# circuitPendulumController01.net
KiCad netlist of a schematic drawn in EAGLE
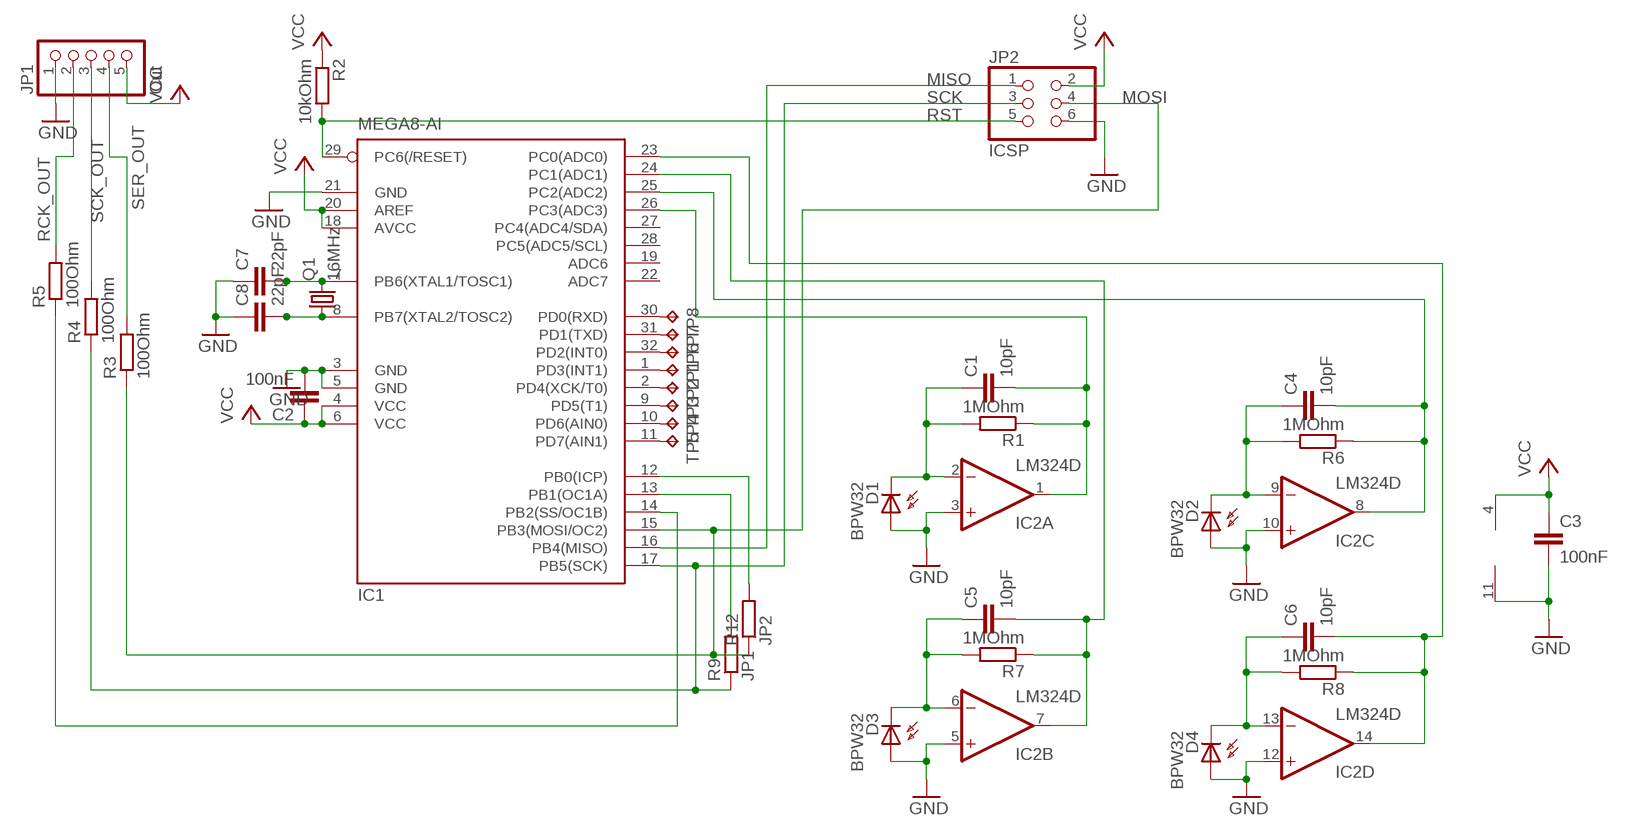
[diagram p0: schematic, sheet 1]

(export (version "E")
  (design (tool "Eeschema 10.0.6"))
  (components
    (comp (ref "C1")
      (value "10pF")
      (footprint "eagle-import:C0603")
      (libsource (lib "eagle-import") (part "C-EUC0603"))
    )
    (comp (ref "C2")
      (value "100nF")
      (footprint "eagle-import:C0603")
      (libsource (lib "eagle-import") (part "C-EUC0603"))
    )
    (comp (ref "C3")
      (value "100nF")
      (footprint "eagle-import:C0603")
      (libsource (lib "eagle-import") (part "C-EUC0603"))
    )
    (comp (ref "C4")
      (value "10pF")
      (footprint "eagle-import:C0603")
      (libsource (lib "eagle-import") (part "C-EUC0603"))
    )
    (comp (ref "C5")
      (value "10pF")
      (footprint "eagle-import:C0603")
      (libsource (lib "eagle-import") (part "C-EUC0603"))
    )
    (comp (ref "C6")
      (value "10pF")
      (footprint "eagle-import:C0603")
      (libsource (lib "eagle-import") (part "C-EUC0603"))
    )
    (comp (ref "C7")
      (value "22pF")
      (footprint "eagle-import:C0603")
      (libsource (lib "eagle-import") (part "C-EUC0603"))
    )
    (comp (ref "C8")
      (value "22pF")
      (footprint "eagle-import:C0603")
      (libsource (lib "eagle-import") (part "C-EUC0603"))
    )
    (comp (ref "D1")
      (value "BPW32")
      (footprint "eagle-import:BPW32")
      (libsource (lib "eagle-import") (part "BPW32"))
    )
    (comp (ref "D2")
      (value "BPW32")
      (footprint "eagle-import:BPW32")
      (libsource (lib "eagle-import") (part "BPW32"))
    )
    (comp (ref "D3")
      (value "BPW32")
      (footprint "eagle-import:BPW32")
      (libsource (lib "eagle-import") (part "BPW32"))
    )
    (comp (ref "D4")
      (value "BPW32")
      (footprint "eagle-import:BPW32")
      (libsource (lib "eagle-import") (part "BPW32"))
    )
    (comp (ref "IC1")
      (value "MEGA8-AI")
      (footprint "eagle-import:TQFP32-08")
      (fields (field (name "MPN") "ATMEGA8-16AU"))
      (libsource (lib "eagle-import") (part "MEGA8-AI"))
    )
    (comp (ref "IC2")
      (value "LM324D")
      (footprint "eagle-import:SO14")
      (libsource (lib "eagle-import") (part "LM324D"))
    )
    (comp (ref "JP1")
      (value "Out")
      (footprint "eagle-import:1_05X2MM")
      (libsource (lib "eagle-import") (part "PINHD-1X55X2MM"))
    )
    (comp (ref "JP2")
      (value "ICSP")
      (footprint "eagle-import:2X03")
      (libsource (lib "eagle-import") (part "PINHD-2X3"))
    )
    (comp (ref "Q1")
      (value "16MHz")
      (footprint "eagle-import:HC49_S")
      (libsource (lib "eagle-import") (part "CRYSTALHC49S"))
    )
    (comp (ref "R1")
      (value "1MOhm")
      (footprint "eagle-import:R0603")
      (libsource (lib "eagle-import") (part "R-EU_R0603"))
    )
    (comp (ref "R2")
      (value "10kOhm")
      (footprint "eagle-import:R0603")
      (libsource (lib "eagle-import") (part "R-EU_R0603"))
    )
    (comp (ref "R3")
      (value "100Ohm")
      (footprint "eagle-import:R0603")
      (libsource (lib "eagle-import") (part "R-EU_R0603"))
    )
    (comp (ref "R4")
      (value "100Ohm")
      (footprint "eagle-import:R0603")
      (libsource (lib "eagle-import") (part "R-EU_R0603"))
    )
    (comp (ref "R5")
      (value "100Ohm")
      (footprint "eagle-import:R0603")
      (libsource (lib "eagle-import") (part "R-EU_R0603"))
    )
    (comp (ref "R6")
      (value "1MOhm")
      (footprint "eagle-import:R0603")
      (libsource (lib "eagle-import") (part "R-EU_R0603"))
    )
    (comp (ref "R7")
      (value "1MOhm")
      (footprint "eagle-import:R0603")
      (libsource (lib "eagle-import") (part "R-EU_R0603"))
    )
    (comp (ref "R8")
      (value "1MOhm")
      (footprint "eagle-import:R0603")
      (libsource (lib "eagle-import") (part "R-EU_R0603"))
    )
    (comp (ref "R9")
      (value "JP1")
      (footprint "eagle-import:R0402")
      (libsource (lib "eagle-import") (part "R-EU_R0402"))
    )
    (comp (ref "R12")
      (value "JP2")
      (footprint "eagle-import:R0402")
      (libsource (lib "eagle-import") (part "R-EU_R0402"))
    )
    (comp (ref "TP1")
      (value "TPTP11R")
      (footprint "eagle-import:TP11R")
      (libsource (lib "eagle-import") (part "TPTP11R"))
    )
    (comp (ref "TP2")
      (value "TPTP11R")
      (footprint "eagle-import:TP11R")
      (libsource (lib "eagle-import") (part "TPTP11R"))
    )
    (comp (ref "TP3")
      (value "TPTP11R")
      (footprint "eagle-import:TP11R")
      (libsource (lib "eagle-import") (part "TPTP11R"))
    )
    (comp (ref "TP4")
      (value "TPTP11R")
      (footprint "eagle-import:TP11R")
      (libsource (lib "eagle-import") (part "TPTP11R"))
    )
    (comp (ref "TP5")
      (value "TPTP11R")
      (footprint "eagle-import:TP11R")
      (libsource (lib "eagle-import") (part "TPTP11R"))
    )
    (comp (ref "TP6")
      (value "TPTP11R")
      (footprint "eagle-import:TP11R")
      (libsource (lib "eagle-import") (part "TPTP11R"))
    )
    (comp (ref "TP7")
      (value "TPTP11R")
      (footprint "eagle-import:TP11R")
      (libsource (lib "eagle-import") (part "TPTP11R"))
    )
    (comp (ref "TP8")
      (value "TPTP11R")
      (footprint "eagle-import:TP11R")
      (libsource (lib "eagle-import") (part "TPTP11R"))
    )
  )
  (nets
    (net (code "1") (name "/MISO") (class "Default")
      (node (ref "IC1") (pin "16") (pinfunction "PB4(MISO)_16") (pintype "bidirectional"))
      (node (ref "JP2") (pin "1") (pinfunction "1_1") (pintype "passive"))
    )
    (net (code "2") (name "/MOSI") (class "Default")
      (node (ref "IC1") (pin "15") (pinfunction "PB3(MOSI/OC2)_15") (pintype "bidirectional"))
      (node (ref "JP2") (pin "4") (pinfunction "4_4") (pintype "passive"))
      (node (ref "R12") (pin "1") (pinfunction "1_1") (pintype "passive"))
      (node (ref "R3") (pin "1") (pinfunction "1_1") (pintype "passive"))
    )
    (net (code "3") (name "/RCK_OUT") (class "Default")
      (node (ref "JP1") (pin "2") (pinfunction "2_2") (pintype "passive"))
      (node (ref "R5") (pin "2") (pinfunction "2_2") (pintype "passive"))
    )
    (net (code "4") (name "/RST") (class "Default")
      (node (ref "IC1") (pin "29") (pinfunction "PC6(/RESET)_29") (pintype "bidirectional"))
      (node (ref "JP2") (pin "5") (pinfunction "5_5") (pintype "passive"))
      (node (ref "R2") (pin "2") (pinfunction "2_2") (pintype "passive"))
    )
    (net (code "5") (name "/SCK") (class "Default")
      (node (ref "IC1") (pin "17") (pinfunction "PB5(SCK)_17") (pintype "bidirectional"))
      (node (ref "JP2") (pin "3") (pinfunction "3_3") (pintype "passive"))
      (node (ref "R4") (pin "1") (pinfunction "1_1") (pintype "passive"))
      (node (ref "R9") (pin "1") (pinfunction "1_1") (pintype "passive"))
    )
    (net (code "6") (name "/SCK_OUT") (class "Default")
      (node (ref "JP1") (pin "3") (pinfunction "3_3") (pintype "passive"))
      (node (ref "R4") (pin "2") (pinfunction "2_2") (pintype "passive"))
    )
    (net (code "7") (name "/SER_OUT") (class "Default")
      (node (ref "JP1") (pin "4") (pinfunction "4_4") (pintype "passive"))
      (node (ref "R3") (pin "2") (pinfunction "2_2") (pintype "passive"))
    )
    (net (code "8") (name "GND") (class "Default")
      (node (ref "C2") (pin "2") (pinfunction "2_2") (pintype "passive"))
      (node (ref "C3") (pin "2") (pinfunction "2_2") (pintype "passive"))
      (node (ref "C7") (pin "1") (pinfunction "1_1") (pintype "passive"))
      (node (ref "C8") (pin "1") (pinfunction "1_1") (pintype "passive"))
      (node (ref "D1") (pin "A") (pinfunction "A_A") (pintype "passive"))
      (node (ref "D2") (pin "A") (pinfunction "A_A") (pintype "passive"))
      (node (ref "D3") (pin "A") (pinfunction "A_A") (pintype "passive"))
      (node (ref "D4") (pin "A") (pinfunction "A_A") (pintype "passive"))
      (node (ref "IC1") (pin "21") (pinfunction "GND_21") (pintype "power_in"))
      (node (ref "IC1") (pin "3") (pinfunction "GND_3") (pintype "power_in"))
      (node (ref "IC1") (pin "5") (pinfunction "GND_5") (pintype "power_in"))
      (node (ref "IC2") (pin "10") (pinfunction "+IN_10") (pintype "input"))
      (node (ref "IC2") (pin "11") (pinfunction "V-_11") (pintype "power_in"))
      (node (ref "IC2") (pin "12") (pinfunction "+IN_12") (pintype "input"))
      (node (ref "IC2") (pin "3") (pinfunction "+IN_3") (pintype "input"))
      (node (ref "IC2") (pin "5") (pinfunction "+IN_5") (pintype "input"))
      (node (ref "JP1") (pin "1") (pinfunction "1_1") (pintype "passive"))
      (node (ref "JP2") (pin "6") (pinfunction "6_6") (pintype "passive"))
    )
    (net (code "9") (name "Net-(D1-C)") (class "Default")
      (node (ref "C1") (pin "1") (pinfunction "1_1") (pintype "passive"))
      (node (ref "D1") (pin "K") (pinfunction "C_K") (pintype "passive"))
      (node (ref "IC2") (pin "2") (pinfunction "-IN_2") (pintype "input"))
      (node (ref "R1") (pin "2") (pinfunction "2_2") (pintype "passive"))
    )
    (net (code "10") (name "Net-(D2-C)") (class "Default")
      (node (ref "C4") (pin "1") (pinfunction "1_1") (pintype "passive"))
      (node (ref "D2") (pin "K") (pinfunction "C_K") (pintype "passive"))
      (node (ref "IC2") (pin "9") (pinfunction "-IN_9") (pintype "input"))
      (node (ref "R6") (pin "2") (pinfunction "2_2") (pintype "passive"))
    )
    (net (code "11") (name "Net-(D3-C)") (class "Default")
      (node (ref "C5") (pin "1") (pinfunction "1_1") (pintype "passive"))
      (node (ref "D3") (pin "K") (pinfunction "C_K") (pintype "passive"))
      (node (ref "IC2") (pin "6") (pinfunction "-IN_6") (pintype "input"))
      (node (ref "R7") (pin "2") (pinfunction "2_2") (pintype "passive"))
    )
    (net (code "12") (name "Net-(D4-C)") (class "Default")
      (node (ref "C6") (pin "1") (pinfunction "1_1") (pintype "passive"))
      (node (ref "D4") (pin "K") (pinfunction "C_K") (pintype "passive"))
      (node (ref "IC2") (pin "13") (pinfunction "-IN_13") (pintype "input"))
      (node (ref "R8") (pin "2") (pinfunction "2_2") (pintype "passive"))
    )
    (net (code "13") (name "Net-(IC1-PB0(ICP))") (class "Default")
      (node (ref "IC1") (pin "12") (pinfunction "PB0(ICP)_12") (pintype "bidirectional"))
      (node (ref "R12") (pin "2") (pinfunction "2_2") (pintype "passive"))
    )
    (net (code "14") (name "Net-(IC1-PB1(OC1A))") (class "Default")
      (node (ref "IC1") (pin "13") (pinfunction "PB1(OC1A)_13") (pintype "bidirectional"))
      (node (ref "R9") (pin "2") (pinfunction "2_2") (pintype "passive"))
    )
    (net (code "15") (name "Net-(IC1-PB2(SS{slash}OC1B))") (class "Default")
      (node (ref "IC1") (pin "14") (pinfunction "PB2(SS/OC1B)_14") (pintype "bidirectional"))
      (node (ref "R5") (pin "1") (pinfunction "1_1") (pintype "passive"))
    )
    (net (code "16") (name "Net-(IC1-PB6(XTAL1{slash}TOSC1))") (class "Default")
      (node (ref "C7") (pin "2") (pinfunction "2_2") (pintype "passive"))
      (node (ref "IC1") (pin "7") (pinfunction "PB6(XTAL1/TOSC1)_7") (pintype "bidirectional"))
      (node (ref "Q1") (pin "2") (pinfunction "2_2") (pintype "passive"))
    )
    (net (code "17") (name "Net-(IC1-PB7(XTAL2{slash}TOSC2))") (class "Default")
      (node (ref "C8") (pin "2") (pinfunction "2_2") (pintype "passive"))
      (node (ref "IC1") (pin "8") (pinfunction "PB7(XTAL2/TOSC2)_8") (pintype "bidirectional"))
      (node (ref "Q1") (pin "1") (pinfunction "1_1") (pintype "passive"))
    )
    (net (code "18") (name "Net-(IC1-PC0(ADC0))") (class "Default")
      (node (ref "C6") (pin "2") (pinfunction "2_2") (pintype "passive"))
      (node (ref "IC1") (pin "23") (pinfunction "PC0(ADC0)_23") (pintype "bidirectional"))
      (node (ref "IC2") (pin "14") (pinfunction "OUT_14") (pintype "output"))
      (node (ref "R8") (pin "1") (pinfunction "1_1") (pintype "passive"))
    )
    (net (code "19") (name "Net-(IC1-PC1(ADC1))") (class "Default")
      (node (ref "C5") (pin "2") (pinfunction "2_2") (pintype "passive"))
      (node (ref "IC1") (pin "24") (pinfunction "PC1(ADC1)_24") (pintype "bidirectional"))
      (node (ref "IC2") (pin "7") (pinfunction "OUT_7") (pintype "output"))
      (node (ref "R7") (pin "1") (pinfunction "1_1") (pintype "passive"))
    )
    (net (code "20") (name "Net-(IC1-PC2(ADC2))") (class "Default")
      (node (ref "C4") (pin "2") (pinfunction "2_2") (pintype "passive"))
      (node (ref "IC1") (pin "25") (pinfunction "PC2(ADC2)_25") (pintype "bidirectional"))
      (node (ref "IC2") (pin "8") (pinfunction "OUT_8") (pintype "output"))
      (node (ref "R6") (pin "1") (pinfunction "1_1") (pintype "passive"))
    )
    (net (code "21") (name "Net-(IC1-PC3(ADC3))") (class "Default")
      (node (ref "C1") (pin "2") (pinfunction "2_2") (pintype "passive"))
      (node (ref "IC1") (pin "26") (pinfunction "PC3(ADC3)_26") (pintype "bidirectional"))
      (node (ref "IC2") (pin "1") (pinfunction "OUT_1") (pintype "output"))
      (node (ref "R1") (pin "1") (pinfunction "1_1") (pintype "passive"))
    )
    (net (code "22") (name "Net-(IC1-PD0(RXD))") (class "Default")
      (node (ref "IC1") (pin "30") (pinfunction "PD0(RXD)_30") (pintype "bidirectional"))
      (node (ref "TP8") (pin "TP") (pinfunction "TP_TP") (pintype "input"))
    )
    (net (code "23") (name "Net-(IC1-PD1(TXD))") (class "Default")
      (node (ref "IC1") (pin "31") (pinfunction "PD1(TXD)_31") (pintype "bidirectional"))
      (node (ref "TP7") (pin "TP") (pinfunction "TP_TP") (pintype "input"))
    )
    (net (code "24") (name "Net-(IC1-PD2(INT0))") (class "Default")
      (node (ref "IC1") (pin "32") (pinfunction "PD2(INT0)_32") (pintype "bidirectional"))
      (node (ref "TP6") (pin "TP") (pinfunction "TP_TP") (pintype "input"))
    )
    (net (code "25") (name "Net-(IC1-PD3(INT1))") (class "Default")
      (node (ref "IC1") (pin "1") (pinfunction "PD3(INT1)_1") (pintype "bidirectional"))
      (node (ref "TP1") (pin "TP") (pinfunction "TP_TP") (pintype "input"))
    )
    (net (code "26") (name "Net-(IC1-PD4(XCK{slash}T0))") (class "Default")
      (node (ref "IC1") (pin "2") (pinfunction "PD4(XCK/T0)_2") (pintype "bidirectional"))
      (node (ref "TP2") (pin "TP") (pinfunction "TP_TP") (pintype "input"))
    )
    (net (code "27") (name "Net-(IC1-PD5(T1))") (class "Default")
      (node (ref "IC1") (pin "9") (pinfunction "PD5(T1)_9") (pintype "bidirectional"))
      (node (ref "TP3") (pin "TP") (pinfunction "TP_TP") (pintype "input"))
    )
    (net (code "28") (name "Net-(IC1-PD6(AIN0))") (class "Default")
      (node (ref "IC1") (pin "10") (pinfunction "PD6(AIN0)_10") (pintype "bidirectional"))
      (node (ref "TP4") (pin "TP") (pinfunction "TP_TP") (pintype "input"))
    )
    (net (code "29") (name "Net-(IC1-PD7(AIN1))") (class "Default")
      (node (ref "IC1") (pin "11") (pinfunction "PD7(AIN1)_11") (pintype "bidirectional"))
      (node (ref "TP5") (pin "TP") (pinfunction "TP_TP") (pintype "input"))
    )
    (net (code "30") (name "VCC") (class "Default")
      (node (ref "C2") (pin "1") (pinfunction "1_1") (pintype "passive"))
      (node (ref "C3") (pin "1") (pinfunction "1_1") (pintype "passive"))
      (node (ref "IC1") (pin "18") (pinfunction "AVCC_18") (pintype "power_in"))
      (node (ref "IC1") (pin "20") (pinfunction "AREF_20") (pintype "passive"))
      (node (ref "IC1") (pin "4") (pinfunction "VCC_4") (pintype "power_in"))
      (node (ref "IC1") (pin "6") (pinfunction "VCC_6") (pintype "power_in"))
      (node (ref "IC2") (pin "4") (pinfunction "V+_4") (pintype "power_in"))
      (node (ref "JP1") (pin "5") (pinfunction "5_5") (pintype "passive"))
      (node (ref "JP2") (pin "2") (pinfunction "2_2") (pintype "passive"))
      (node (ref "R2") (pin "1") (pinfunction "1_1") (pintype "passive"))
    )
    (net (code "31") (name "unconnected-(IC1-ADC6-Pad19)") (class "Default")
      (node (ref "IC1") (pin "19") (pinfunction "ADC6_19") (pintype "bidirectional"))
    )
    (net (code "32") (name "unconnected-(IC1-ADC7-Pad22)") (class "Default")
      (node (ref "IC1") (pin "22") (pinfunction "ADC7_22") (pintype "bidirectional"))
    )
    (net (code "33") (name "unconnected-(IC1-PC4(ADC4{slash}SDA)-Pad27)") (class "Default")
      (node (ref "IC1") (pin "27") (pinfunction "PC4(ADC4/SDA)_27") (pintype "bidirectional"))
    )
    (net (code "34") (name "unconnected-(IC1-PC5(ADC5{slash}SCL)-Pad28)") (class "Default")
      (node (ref "IC1") (pin "28") (pinfunction "PC5(ADC5/SCL)_28") (pintype "bidirectional"))
    )
  )
)
